# 3_5.net
KiCad netlist of a schematic drawn in Altium Designer
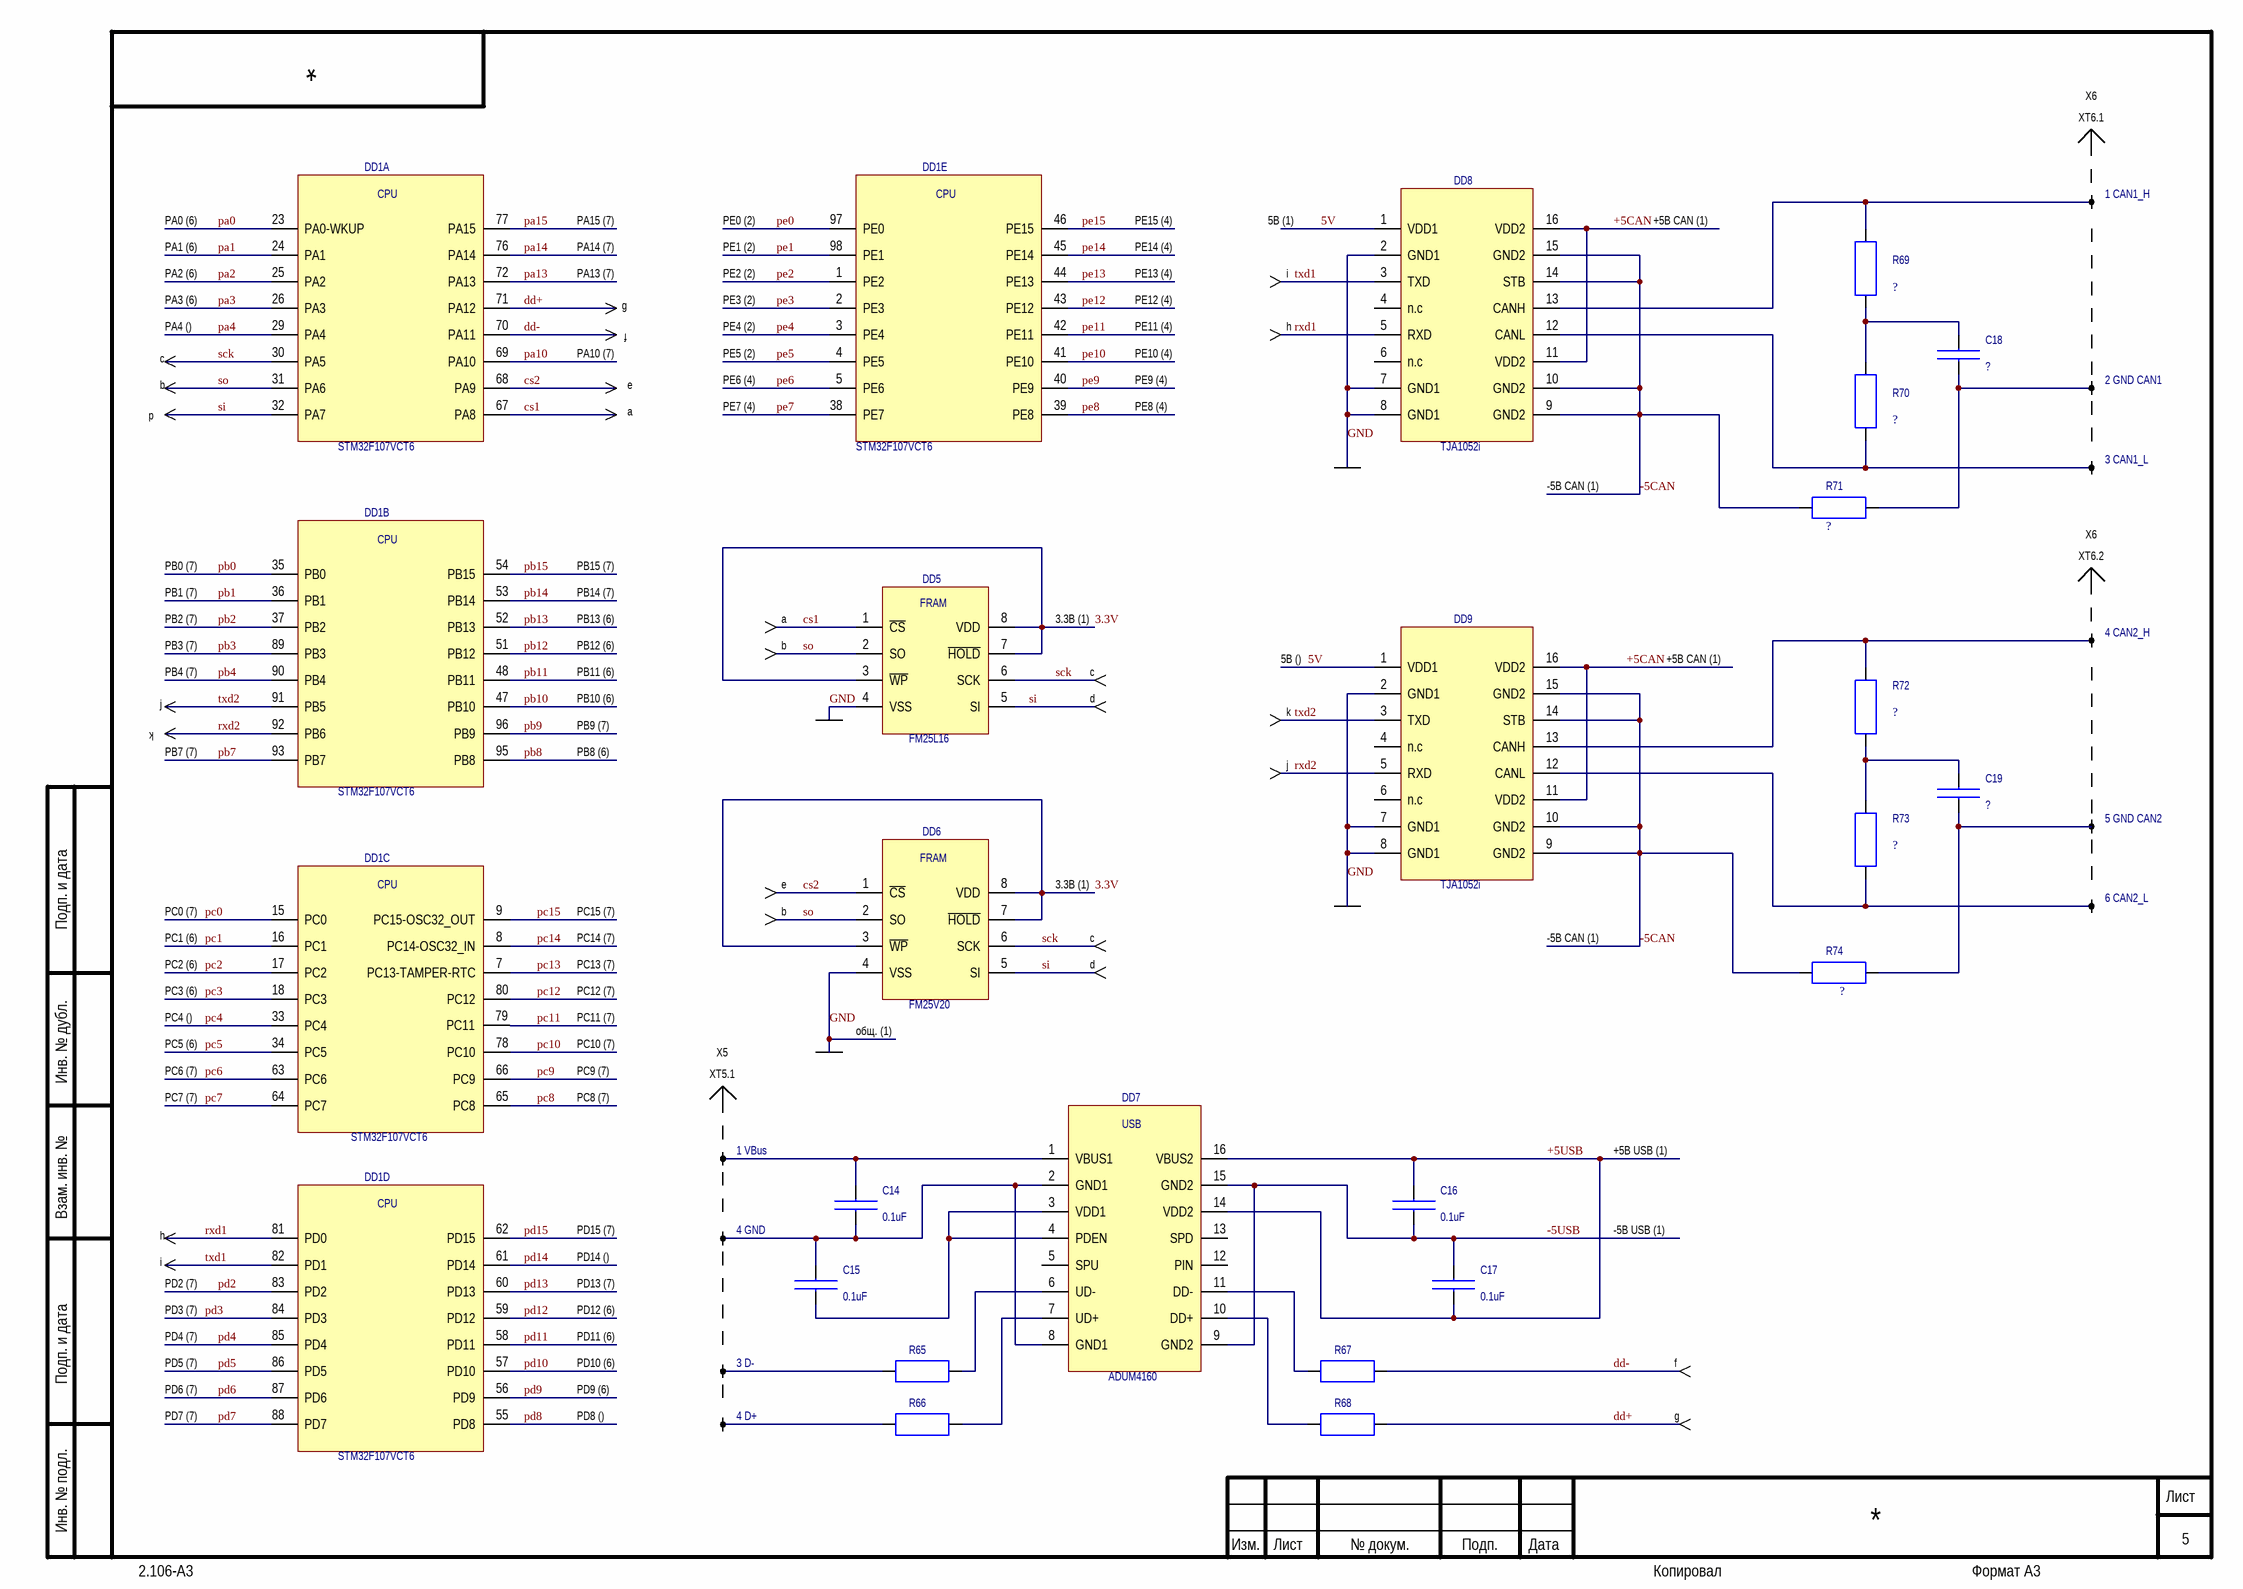
[diagram p0: Э3_5.SchDoc]

(export (version "E")
  (design (tool "Eeschema 10.0.6"))
  (components
    (comp (ref "C14") (value "0.1uF") (footprint "PcbLib1:CAP0805") (libsource (lib "Schlib1") (part "C")))
    (comp (ref "C15") (value "0.1uF") (footprint "PcbLib1:CAP0805") (libsource (lib "Schlib1") (part "C")))
    (comp (ref "C16") (value "0.1uF") (footprint "PcbLib1:CAP0805") (libsource (lib "Schlib1") (part "C")))
    (comp (ref "C17") (value "0.1uF") (footprint "PcbLib1:CAP0805") (libsource (lib "Schlib1") (part "C")))
    (comp (ref "C18") (value "?") (footprint "PcbLib1:CAP0805") (libsource (lib "Schlib1") (part "C")))
    (comp (ref "C19") (value "?") (footprint "PcbLib1:CAP0805") (libsource (lib "Schlib1") (part "C")))
    (comp (ref "DD1")
      (value "STM32F107VCT6")
      (footprint "PcbLib1:LQFP100_N")
      (libsource (lib "Schlib1") (part "STM32F107VCT6_1"))
    )
    (comp (ref "DD5")
      (value "FM25L16")
      (footprint "PcbLib1:SOIC127P600X175-8N")
      (libsource (lib "Schlib1") (part "FM25L16"))
    )
    (comp (ref "DD6")
      (value "FM25V20")
      (footprint "PcbLib1:SOIC127P800X203-8N")
      (libsource (lib "Schlib1") (part "FM25V20"))
    )
    (comp (ref "DD7")
      (value "ADUM4160")
      (footprint "PcbLib1:SOIC127P1030X265-16N")
      (libsource (lib "Schlib1") (part "ADUM4160"))
    )
    (comp (ref "DD8")
      (value "TJA1052i")
      (footprint "PcbLib1:SOP127P1030X265-16N")
      (libsource (lib "Schlib1") (part "TJA1052i"))
    )
    (comp (ref "DD9")
      (value "TJA1052i")
      (footprint "PcbLib1:SOP127P1030X265-16N")
      (libsource (lib "Schlib1") (part "TJA1052i"))
    )
    (comp (ref "R65") (value "24") (footprint "PcbLib1:RES0805") (libsource (lib "Schlib1") (part "R")))
    (comp (ref "R66") (value "24") (footprint "PcbLib1:RES0805") (libsource (lib "Schlib1") (part "R")))
    (comp (ref "R67") (value "24") (footprint "PcbLib1:RES0805") (libsource (lib "Schlib1") (part "R")))
    (comp (ref "R68") (value "24") (footprint "PcbLib1:RES0805") (libsource (lib "Schlib1") (part "R")))
    (comp (ref "R69") (value "?") (footprint "PcbLib1:RES0805") (libsource (lib "Schlib1") (part "R")))
    (comp (ref "R70") (value "?") (footprint "PcbLib1:RES0805") (libsource (lib "Schlib1") (part "R")))
    (comp (ref "R71") (value "?") (footprint "PcbLib1:RES0805") (libsource (lib "Schlib1") (part "R")))
    (comp (ref "R72") (value "?") (footprint "PcbLib1:RES0805") (libsource (lib "Schlib1") (part "R")))
    (comp (ref "R73") (value "?") (footprint "PcbLib1:RES0805") (libsource (lib "Schlib1") (part "R")))
    (comp (ref "R74") (value "?") (footprint "PcbLib1:RES0805") (libsource (lib "Schlib1") (part "R")))
    (comp (ref "X5") (value "1 VBus") (footprint "PcbLib1:usbB") (libsource (lib "Schlib1") (part "USBB-1J")))
    (comp (ref "X6")
      (value "1 CAN1_H")
      (footprint "PcbLib1:PLD10")
      (libsource (lib "Schlib1") (part "PLD10"))
    )
  )
  (nets
    (net (code "1") (name "/+5CAN") (class "Default")
      (node (ref "DD8") (pin "11") (pinfunction "VDD2_11") (pintype "passive"))
      (node (ref "DD8") (pin "16") (pinfunction "VDD2_16") (pintype "passive"))
      (node (ref "DD9") (pin "11") (pinfunction "VDD2_11") (pintype "passive"))
      (node (ref "DD9") (pin "16") (pinfunction "VDD2_16") (pintype "passive"))
    )
    (net (code "2") (name "/+5USB") (class "Default")
      (node (ref "C16") (pin "2") (pintype "passive"))
      (node (ref "C17") (pin "1") (pintype "passive"))
      (node (ref "DD7") (pin "14") (pinfunction "VDD2_14") (pintype "passive"))
      (node (ref "DD7") (pin "16") (pinfunction "VBUS2_16") (pintype "passive"))
    )
    (net (code "3") (name "/-5CAN") (class "Default")
      (node (ref "DD8") (pin "10") (pinfunction "GND2_10") (pintype "passive"))
      (node (ref "DD8") (pin "14") (pinfunction "STB_14") (pintype "passive"))
      (node (ref "DD8") (pin "15") (pinfunction "GND2_15") (pintype "passive"))
      (node (ref "DD8") (pin "9") (pinfunction "GND2_9") (pintype "passive"))
      (node (ref "DD9") (pin "10") (pinfunction "GND2_10") (pintype "passive"))
      (node (ref "DD9") (pin "14") (pinfunction "STB_14") (pintype "passive"))
      (node (ref "DD9") (pin "15") (pinfunction "GND2_15") (pintype "passive"))
      (node (ref "DD9") (pin "9") (pinfunction "GND2_9") (pintype "passive"))
      (node (ref "R71") (pin "2") (pintype "passive"))
      (node (ref "R74") (pin "2") (pintype "passive"))
    )
    (net (code "4") (name "/-5USB") (class "Default")
      (node (ref "C16") (pin "1") (pintype "passive"))
      (node (ref "C17") (pin "2") (pintype "passive"))
      (node (ref "DD7") (pin "15") (pinfunction "GND2_15") (pintype "passive"))
      (node (ref "DD7") (pin "9") (pinfunction "GND2_9") (pintype "passive"))
    )
    (net (code "5") (name "/3.3V") (class "Default")
      (node (ref "DD5") (pin "3") (pinfunction "~{WP}_3") (pintype "passive"))
      (node (ref "DD5") (pin "7") (pinfunction "~{HOLD}_7") (pintype "passive"))
      (node (ref "DD5") (pin "8") (pinfunction "VDD_8") (pintype "passive"))
      (node (ref "DD6") (pin "3") (pinfunction "~{WP}_3") (pintype "passive"))
      (node (ref "DD6") (pin "7") (pinfunction "~{HOLD}_7") (pintype "passive"))
      (node (ref "DD6") (pin "8") (pinfunction "VDD_8") (pintype "passive"))
    )
    (net (code "6") (name "/5V") (class "Default")
      (node (ref "DD8") (pin "1") (pinfunction "VDD1_1") (pintype "passive"))
      (node (ref "DD9") (pin "1") (pinfunction "VDD1_1") (pintype "passive"))
    )
    (net (code "7") (name "/GND") (class "Default")
      (node (ref "DD5") (pin "4") (pinfunction "VSS_4") (pintype "passive"))
      (node (ref "DD6") (pin "4") (pinfunction "VSS_4") (pintype "passive"))
      (node (ref "DD8") (pin "2") (pinfunction "GND1_2") (pintype "passive"))
      (node (ref "DD8") (pin "7") (pinfunction "GND1_7") (pintype "passive"))
      (node (ref "DD8") (pin "8") (pinfunction "GND1_8") (pintype "passive"))
      (node (ref "DD9") (pin "2") (pinfunction "GND1_2") (pintype "passive"))
      (node (ref "DD9") (pin "7") (pinfunction "GND1_7") (pintype "passive"))
      (node (ref "DD9") (pin "8") (pinfunction "GND1_8") (pintype "passive"))
    )
    (net (code "8") (name "/cs1") (class "Default")
      (node (ref "DD1") (pin "67") (pinfunction "PA8_67") (pintype "passive"))
      (node (ref "DD5") (pin "1") (pinfunction "~{CS}_1") (pintype "passive"))
    )
    (net (code "9") (name "/cs2") (class "Default")
      (node (ref "DD1") (pin "68") (pinfunction "PA9_68") (pintype "passive"))
      (node (ref "DD6") (pin "1") (pinfunction "~{CS}_1") (pintype "passive"))
    )
    (net (code "10") (name "/dd+") (class "Default")
      (node (ref "DD1") (pin "71") (pinfunction "PA12_71") (pintype "passive"))
      (node (ref "R68") (pin "1") (pintype "passive"))
    )
    (net (code "11") (name "/dd-") (class "Default")
      (node (ref "DD1") (pin "70") (pinfunction "PA11_70") (pintype "passive"))
      (node (ref "R67") (pin "1") (pintype "passive"))
    )
    (net (code "12") (name "/pa0") (class "Default")
      (node (ref "DD1") (pin "23") (pinfunction "PA0-WKUP_23") (pintype "passive"))
    )
    (net (code "13") (name "/pa1") (class "Default")
      (node (ref "DD1") (pin "24") (pinfunction "PA1_24") (pintype "passive"))
    )
    (net (code "14") (name "/pa2") (class "Default")
      (node (ref "DD1") (pin "25") (pinfunction "PA2_25") (pintype "passive"))
    )
    (net (code "15") (name "/pa3") (class "Default")
      (node (ref "DD1") (pin "26") (pinfunction "PA3_26") (pintype "passive"))
    )
    (net (code "16") (name "/pa4") (class "Default")
      (node (ref "DD1") (pin "29") (pinfunction "PA4_29") (pintype "passive"))
    )
    (net (code "17") (name "/pa10") (class "Default")
      (node (ref "DD1") (pin "69") (pinfunction "PA10_69") (pintype "passive"))
    )
    (net (code "18") (name "/pa13") (class "Default")
      (node (ref "DD1") (pin "72") (pinfunction "PA13_72") (pintype "passive"))
    )
    (net (code "19") (name "/pa14") (class "Default")
      (node (ref "DD1") (pin "76") (pinfunction "PA14_76") (pintype "passive"))
    )
    (net (code "20") (name "/pa15") (class "Default")
      (node (ref "DD1") (pin "77") (pinfunction "PA15_77") (pintype "passive"))
    )
    (net (code "21") (name "/pb0") (class "Default")
      (node (ref "DD1") (pin "35") (pinfunction "PB0_35") (pintype "passive"))
    )
    (net (code "22") (name "/pb1") (class "Default")
      (node (ref "DD1") (pin "36") (pinfunction "PB1_36") (pintype "passive"))
    )
    (net (code "23") (name "/pb2") (class "Default")
      (node (ref "DD1") (pin "37") (pinfunction "PB2_37") (pintype "passive"))
    )
    (net (code "24") (name "/pb3") (class "Default")
      (node (ref "DD1") (pin "89") (pinfunction "PB3_89") (pintype "passive"))
    )
    (net (code "25") (name "/pb4") (class "Default")
      (node (ref "DD1") (pin "90") (pinfunction "PB4_90") (pintype "passive"))
    )
    (net (code "26") (name "/pb7") (class "Default")
      (node (ref "DD1") (pin "93") (pinfunction "PB7_93") (pintype "passive"))
    )
    (net (code "27") (name "/pb8") (class "Default")
      (node (ref "DD1") (pin "95") (pinfunction "PB8_95") (pintype "passive"))
    )
    (net (code "28") (name "/pb9") (class "Default")
      (node (ref "DD1") (pin "96") (pinfunction "PB9_96") (pintype "passive"))
    )
    (net (code "29") (name "/pb10") (class "Default")
      (node (ref "DD1") (pin "47") (pinfunction "PB10_47") (pintype "passive"))
    )
    (net (code "30") (name "/pb11") (class "Default")
      (node (ref "DD1") (pin "48") (pinfunction "PB11_48") (pintype "passive"))
    )
    (net (code "31") (name "/pb12") (class "Default")
      (node (ref "DD1") (pin "51") (pinfunction "PB12_51") (pintype "passive"))
    )
    (net (code "32") (name "/pb13") (class "Default")
      (node (ref "DD1") (pin "52") (pinfunction "PB13_52") (pintype "passive"))
    )
    (net (code "33") (name "/pb14") (class "Default")
      (node (ref "DD1") (pin "53") (pinfunction "PB14_53") (pintype "passive"))
    )
    (net (code "34") (name "/pb15") (class "Default")
      (node (ref "DD1") (pin "54") (pinfunction "PB15_54") (pintype "passive"))
    )
    (net (code "35") (name "/pc0") (class "Default")
      (node (ref "DD1") (pin "15") (pinfunction "PC0_15") (pintype "passive"))
    )
    (net (code "36") (name "/pc1") (class "Default")
      (node (ref "DD1") (pin "16") (pinfunction "PC1_16") (pintype "passive"))
    )
    (net (code "37") (name "/pc2") (class "Default")
      (node (ref "DD1") (pin "17") (pinfunction "PC2_17") (pintype "passive"))
    )
    (net (code "38") (name "/pc3") (class "Default")
      (node (ref "DD1") (pin "18") (pinfunction "PC3_18") (pintype "passive"))
    )
    (net (code "39") (name "/pc4") (class "Default")
      (node (ref "DD1") (pin "33") (pinfunction "PC4_33") (pintype "passive"))
    )
    (net (code "40") (name "/pc5") (class "Default")
      (node (ref "DD1") (pin "34") (pinfunction "PC5_34") (pintype "passive"))
    )
    (net (code "41") (name "/pc6") (class "Default")
      (node (ref "DD1") (pin "63") (pinfunction "PC6_63") (pintype "passive"))
    )
    (net (code "42") (name "/pc7") (class "Default")
      (node (ref "DD1") (pin "64") (pinfunction "PC7_64") (pintype "passive"))
    )
    (net (code "43") (name "/pc8") (class "Default")
      (node (ref "DD1") (pin "65") (pinfunction "PC8_65") (pintype "passive"))
    )
    (net (code "44") (name "/pc9") (class "Default")
      (node (ref "DD1") (pin "66") (pinfunction "PC9_66") (pintype "passive"))
    )
    (net (code "45") (name "/pc10") (class "Default")
      (node (ref "DD1") (pin "78") (pinfunction "PC10_78") (pintype "passive"))
    )
    (net (code "47") (name "/pc12") (class "Default")
      (node (ref "DD1") (pin "80") (pinfunction "PC12_80") (pintype "passive"))
    )
    (net (code "48") (name "/pc13") (class "Default")
      (node (ref "DD1") (pin "7") (pinfunction "PC13-TAMPER-RTC_7") (pintype "passive"))
    )
    (net (code "49") (name "/pc14") (class "Default")
      (node (ref "DD1") (pin "8") (pinfunction "PC14-OSC32_IN_8") (pintype "passive"))
    )
    (net (code "50") (name "/pc15") (class "Default")
      (node (ref "DD1") (pin "9") (pinfunction "PC15-OSC32_OUT_9") (pintype "passive"))
    )
    (net (code "51") (name "/pd2") (class "Default")
      (node (ref "DD1") (pin "83") (pinfunction "PD2_83") (pintype "passive"))
    )
    (net (code "52") (name "/pd3") (class "Default")
      (node (ref "DD1") (pin "84") (pinfunction "PD3_84") (pintype "passive"))
    )
    (net (code "53") (name "/pd4") (class "Default")
      (node (ref "DD1") (pin "85") (pinfunction "PD4_85") (pintype "passive"))
    )
    (net (code "54") (name "/pd5") (class "Default")
      (node (ref "DD1") (pin "86") (pinfunction "PD5_86") (pintype "passive"))
    )
    (net (code "55") (name "/pd6") (class "Default")
      (node (ref "DD1") (pin "87") (pinfunction "PD6_87") (pintype "passive"))
    )
    (net (code "56") (name "/pd7") (class "Default")
      (node (ref "DD1") (pin "88") (pinfunction "PD7_88") (pintype "passive"))
    )
    (net (code "57") (name "/pd8") (class "Default")
      (node (ref "DD1") (pin "55") (pinfunction "PD8_55") (pintype "passive"))
    )
    (net (code "58") (name "/pd9") (class "Default")
      (node (ref "DD1") (pin "56") (pinfunction "PD9_56") (pintype "passive"))
    )
    (net (code "59") (name "/pd10") (class "Default")
      (node (ref "DD1") (pin "57") (pinfunction "PD10_57") (pintype "passive"))
    )
    (net (code "60") (name "/pd11") (class "Default")
      (node (ref "DD1") (pin "58") (pinfunction "PD11_58") (pintype "passive"))
    )
    (net (code "61") (name "/pd12") (class "Default")
      (node (ref "DD1") (pin "59") (pinfunction "PD12_59") (pintype "passive"))
    )
    (net (code "62") (name "/pd13") (class "Default")
      (node (ref "DD1") (pin "60") (pinfunction "PD13_60") (pintype "passive"))
    )
    (net (code "63") (name "/pd14") (class "Default")
      (node (ref "DD1") (pin "61") (pinfunction "PD14_61") (pintype "passive"))
    )
    (net (code "64") (name "/pd15") (class "Default")
      (node (ref "DD1") (pin "62") (pinfunction "PD15_62") (pintype "passive"))
    )
    (net (code "65") (name "/pe0") (class "Default")
      (node (ref "DD1") (pin "97") (pinfunction "PE0_97") (pintype "passive"))
    )
    (net (code "66") (name "/pe1") (class "Default")
      (node (ref "DD1") (pin "98") (pinfunction "PE1_98") (pintype "passive"))
    )
    (net (code "67") (name "/pe2") (class "Default")
      (node (ref "DD1") (pin "1") (pinfunction "PE2_1") (pintype "passive"))
    )
    (net (code "68") (name "/pe3") (class "Default")
      (node (ref "DD1") (pin "2") (pinfunction "PE3_2") (pintype "passive"))
    )
    (net (code "69") (name "/pe4") (class "Default")
      (node (ref "DD1") (pin "3") (pinfunction "PE4_3") (pintype "passive"))
    )
    (net (code "70") (name "/pe5") (class "Default")
      (node (ref "DD1") (pin "4") (pinfunction "PE5_4") (pintype "passive"))
    )
    (net (code "71") (name "/pe6") (class "Default")
      (node (ref "DD1") (pin "5") (pinfunction "PE6_5") (pintype "passive"))
    )
    (net (code "72") (name "/pe7") (class "Default")
      (node (ref "DD1") (pin "38") (pinfunction "PE7_38") (pintype "passive"))
    )
    (net (code "73") (name "/pe8") (class "Default")
      (node (ref "DD1") (pin "39") (pinfunction "PE8_39") (pintype "passive"))
    )
    (net (code "74") (name "/pe9") (class "Default")
      (node (ref "DD1") (pin "40") (pinfunction "PE9_40") (pintype "passive"))
    )
    (net (code "75") (name "/pe10") (class "Default")
      (node (ref "DD1") (pin "41") (pinfunction "PE10_41") (pintype "passive"))
    )
    (net (code "76") (name "/pe11") (class "Default")
      (node (ref "DD1") (pin "42") (pinfunction "PE11_42") (pintype "passive"))
    )
    (net (code "77") (name "/pe12") (class "Default")
      (node (ref "DD1") (pin "43") (pinfunction "PE12_43") (pintype "passive"))
    )
    (net (code "78") (name "/pe13") (class "Default")
      (node (ref "DD1") (pin "44") (pinfunction "PE13_44") (pintype "passive"))
    )
    (net (code "79") (name "/pe14") (class "Default")
      (node (ref "DD1") (pin "45") (pinfunction "PE14_45") (pintype "passive"))
    )
    (net (code "80") (name "/pe15") (class "Default")
      (node (ref "DD1") (pin "46") (pinfunction "PE15_46") (pintype "passive"))
    )
    (net (code "81") (name "/rxd1") (class "Default")
      (node (ref "DD1") (pin "81") (pinfunction "PD0_81") (pintype "passive"))
      (node (ref "DD8") (pin "5") (pinfunction "RXD_5") (pintype "passive"))
    )
    (net (code "82") (name "/rxd2") (class "Default")
      (node (ref "DD1") (pin "92") (pinfunction "PB6_92") (pintype "passive"))
      (node (ref "DD9") (pin "5") (pinfunction "RXD_5") (pintype "passive"))
    )
    (net (code "83") (name "/sck") (class "Default")
      (node (ref "DD1") (pin "30") (pinfunction "PA5_30") (pintype "passive"))
      (node (ref "DD5") (pin "6") (pinfunction "SCK_6") (pintype "passive"))
      (node (ref "DD6") (pin "6") (pinfunction "SCK_6") (pintype "passive"))
    )
    (net (code "84") (name "/si") (class "Default")
      (node (ref "DD1") (pin "32") (pinfunction "PA7_32") (pintype "passive"))
      (node (ref "DD5") (pin "5") (pinfunction "SI_5") (pintype "passive"))
      (node (ref "DD6") (pin "5") (pinfunction "SI_5") (pintype "passive"))
    )
    (net (code "85") (name "/so") (class "Default")
      (node (ref "DD1") (pin "31") (pinfunction "PA6_31") (pintype "passive"))
      (node (ref "DD5") (pin "2") (pinfunction "SO_2") (pintype "passive"))
      (node (ref "DD6") (pin "2") (pinfunction "SO_2") (pintype "passive"))
    )
    (net (code "86") (name "/txd1") (class "Default")
      (node (ref "DD1") (pin "82") (pinfunction "PD1_82") (pintype "passive"))
      (node (ref "DD8") (pin "3") (pinfunction "TXD_3") (pintype "passive"))
    )
    (net (code "87") (name "/txd2") (class "Default")
      (node (ref "DD1") (pin "91") (pinfunction "PB5_91") (pintype "passive"))
      (node (ref "DD9") (pin "3") (pinfunction "TXD_3") (pintype "passive"))
    )
    (net (code "88") (name "Net-(C18-Pad2)") (class "Default")
      (node (ref "C18") (pin "2") (pintype "passive"))
      (node (ref "R69") (pin "1") (pintype "passive"))
      (node (ref "R70") (pin "2") (pintype "passive"))
    )
    (net (code "89") (name "Net-(C19-Pad2)") (class "Default")
      (node (ref "C19") (pin "2") (pintype "passive"))
      (node (ref "R72") (pin "1") (pintype "passive"))
      (node (ref "R73") (pin "2") (pintype "passive"))
    )
    (net (code "90") (name "Net-(DD7-DD+)") (class "Default")
      (node (ref "DD7") (pin "10") (pinfunction "DD+_10") (pintype "passive"))
      (node (ref "R68") (pin "2") (pintype "passive"))
    )
    (net (code "91") (name "Net-(DD7-DD-)") (class "Default")
      (node (ref "DD7") (pin "11") (pinfunction "DD-_11") (pintype "passive"))
      (node (ref "R67") (pin "2") (pintype "passive"))
    )
    (net (code "92") (name "Net-(DD7-PDEN)") (class "Default")
      (node (ref "C15") (pin "1") (pintype "passive"))
      (node (ref "DD7") (pin "3") (pinfunction "VDD1_3") (pintype "passive"))
      (node (ref "DD7") (pin "4") (pinfunction "PDEN_4") (pintype "passive"))
    )
    (net (code "93") (name "Net-(DD7-UD+)") (class "Default")
      (node (ref "DD7") (pin "7") (pinfunction "UD+_7") (pintype "passive"))
      (node (ref "R66") (pin "2") (pintype "passive"))
    )
    (net (code "94") (name "Net-(DD7-UD-)") (class "Default")
      (node (ref "DD7") (pin "6") (pinfunction "UD-_6") (pintype "passive"))
      (node (ref "R65") (pin "2") (pintype "passive"))
    )
    (net (code "95") (name "Net-(DD7-VBUS1)") (class "Default")
      (node (ref "C14") (pin "2") (pintype "passive"))
      (node (ref "DD7") (pin "1") (pinfunction "VBUS1_1") (pintype "passive"))
      (node (ref "X5") (pin "1") (pinfunction "1_1") (pintype "passive"))
    )
    (net (code "96") (name "Net-(DD8-CANH)") (class "Default")
      (node (ref "DD8") (pin "13") (pinfunction "CANH_13") (pintype "passive"))
      (node (ref "R69") (pin "2") (pintype "passive"))
      (node (ref "X6") (pin "1") (pinfunction "1_1") (pintype "passive"))
    )
    (net (code "97") (name "Net-(DD8-CANL)") (class "Default")
      (node (ref "DD8") (pin "12") (pinfunction "CANL_12") (pintype "passive"))
      (node (ref "R70") (pin "1") (pintype "passive"))
      (node (ref "X6") (pin "3") (pinfunction "1_3") (pintype "passive"))
    )
    (net (code "98") (name "Net-(DD9-CANH)") (class "Default")
      (node (ref "DD9") (pin "13") (pinfunction "CANH_13") (pintype "passive"))
      (node (ref "R72") (pin "2") (pintype "passive"))
      (node (ref "X6") (pin "4") (pinfunction "1_4") (pintype "passive"))
    )
    (net (code "99") (name "Net-(DD9-CANL)") (class "Default")
      (node (ref "DD9") (pin "12") (pinfunction "CANL_12") (pintype "passive"))
      (node (ref "R73") (pin "1") (pintype "passive"))
      (node (ref "X6") (pin "6") (pinfunction "1_6") (pintype "passive"))
    )
    (net (code "100") (name "Net-(X5B-1)") (class "Default")
      (node (ref "R66") (pin "1") (pintype "passive"))
      (node (ref "X5") (pin "2") (pinfunction "1_2") (pintype "passive"))
    )
    (net (code "101") (name "Net-(X5C-1)") (class "Default")
      (node (ref "R65") (pin "1") (pintype "passive"))
      (node (ref "X5") (pin "3") (pinfunction "1_3") (pintype "passive"))
    )
    (net (code "102") (name "Net-(X5D-1)") (class "Default")
      (node (ref "C14") (pin "1") (pintype "passive"))
      (node (ref "C15") (pin "2") (pintype "passive"))
      (node (ref "DD7") (pin "2") (pinfunction "GND1_2") (pintype "passive"))
      (node (ref "DD7") (pin "8") (pinfunction "GND1_8") (pintype "passive"))
      (node (ref "X5") (pin "4") (pinfunction "1_4") (pintype "passive"))
    )
    (net (code "103") (name "Net-(X6B-1)") (class "Default")
      (node (ref "C18") (pin "1") (pintype "passive"))
      (node (ref "R71") (pin "1") (pintype "passive"))
      (node (ref "X6") (pin "2") (pinfunction "1_2") (pintype "passive"))
    )
    (net (code "104") (name "Net-(X6E-1)") (class "Default")
      (node (ref "C19") (pin "1") (pintype "passive"))
      (node (ref "R74") (pin "1") (pintype "passive"))
      (node (ref "X6") (pin "5") (pinfunction "1_5") (pintype "passive"))
    )
    (net (code "105") (name "unconnected-(DD1C-PC11-Pad79)") (class "Default")
      (node (ref "DD1") (pin "79") (pinfunction "PC11_79") (pintype "passive"))
    )
    (net (code "106") (name "unconnected-(DD7-PIN-Pad12)") (class "Default")
      (node (ref "DD7") (pin "12") (pinfunction "PIN_12") (pintype "passive"))
    )
    (net (code "107") (name "unconnected-(DD7-SPD-Pad13)") (class "Default")
      (node (ref "DD7") (pin "13") (pinfunction "SPD_13") (pintype "passive"))
    )
    (net (code "108") (name "unconnected-(DD7-SPU-Pad5)") (class "Default")
      (node (ref "DD7") (pin "5") (pinfunction "SPU_5") (pintype "passive"))
    )
    (net (code "109") (name "unconnected-(DD8-n.c-Pad4)") (class "Default")
      (node (ref "DD8") (pin "4") (pinfunction "n.c_4") (pintype "passive"))
    )
    (net (code "110") (name "unconnected-(DD8-n.c-Pad6)") (class "Default")
      (node (ref "DD8") (pin "6") (pinfunction "n.c_6") (pintype "passive"))
    )
    (net (code "111") (name "unconnected-(DD9-n.c-Pad4)") (class "Default")
      (node (ref "DD9") (pin "4") (pinfunction "n.c_4") (pintype "passive"))
    )
    (net (code "112") (name "unconnected-(DD9-n.c-Pad6)") (class "Default")
      (node (ref "DD9") (pin "6") (pinfunction "n.c_6") (pintype "passive"))
    )
  )
)
